# power_connector.net
KiCad netlist of a schematic drawn in Altium Designer
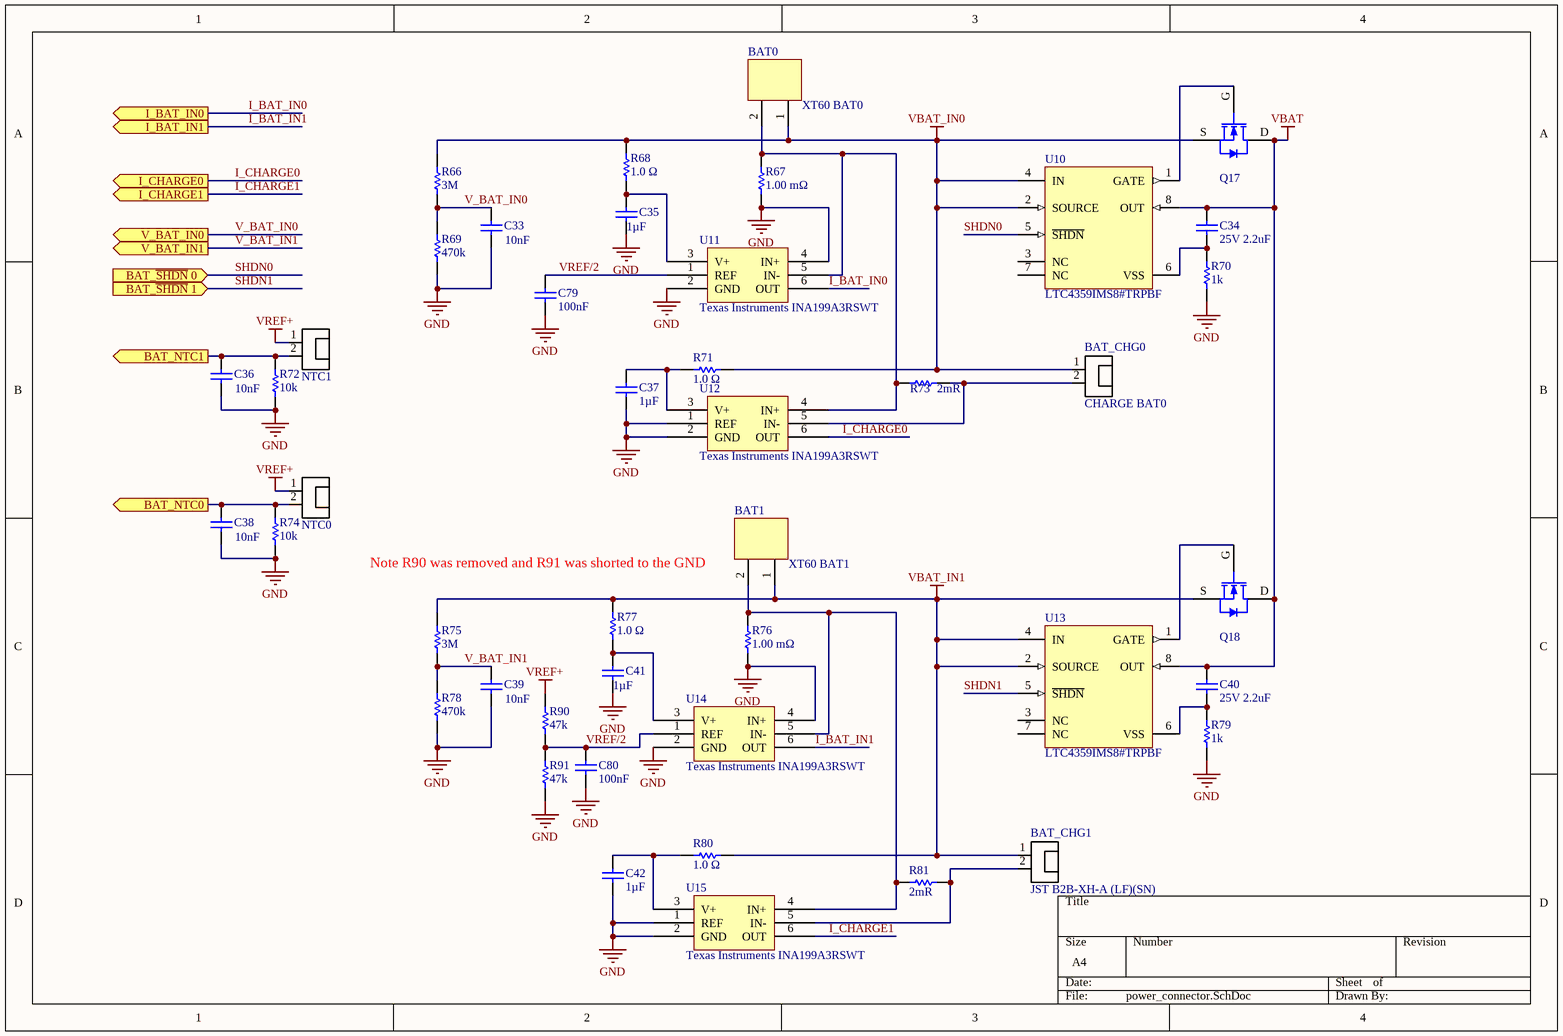
[diagram p0: power_connector.SchDoc]

(export (version "E")
  (design (tool "Eeschema 10.0.6"))
  (components
    (comp (ref "BAT0")
      (value "XT60 BAT0")
      (footprint "PCB-8tmbcd94dx0l5ponnqur-1")
      (description "XT60 Connector Male")
      (libsource (lib "CommunityVault") (part "CMP-d8151592827e07d2-9"))
    )
    (comp (ref "BAT1")
      (value "XT60 BAT1")
      (footprint "PCB-8tmbcd94dx0l5ponnqur-1")
      (description "XT60 Connector Male")
      (libsource (lib "CommunityVault") (part "CMP-d8151592827e07d2-9"))
    )
    (comp (ref "BAT_CHG0")
      (value "CHARGE BAT0")
      (footprint "PCB-s8s8ac3ylnu6waak0fxh-1")
      (description "XH Series 2 Position 2.5 mm Pitch Through Hole Top Entry Shrouded Header")
      (fields (field (name "MANUFACTURER PART NUMBER") "B2B-XH-A (LF)(SN)"))
      (libsource (lib "CommunityVault") (part "SYM-a2a66bdac84f7d61-1"))
    )
    (comp (ref "BAT_CHG1")
      (value "JST B2B-XH-A (LF)(SN)")
      (footprint "PCB-s8s8ac3ylnu6waak0fxh-1")
      (description "XH Series 2 Position 2.5 mm Pitch Through Hole Top Entry Shrouded Header")
      (fields (field (name "MANUFACTURER PART NUMBER") "B2B-XH-A (LF)(SN)"))
      (libsource (lib "CommunityVault") (part "SYM-a2a66bdac84f7d61-1"))
    )
    (comp (ref "C33")
      (value "10nF")
      (footprint "RESC1005X40X25LL05T05")
      (description "0.01uF Capacitor")
      (fields (field (name "MANUFACTURER PART NUMBER") "04025C103KAT2A"))
      (libsource (lib "CommunityVault") (part "CMP-16527022-3"))
    )
    (comp (ref "C34")
      (value "25V 2.2uF")
      (footprint "C0805")
      (description "0805 2.2 uF 25 V ±10 % Tolerance X7R SMT Multilayer Ceramic Capacitor")
      (fields (field (name "MANUFACTURER PART NUMBER") "CC0805KKX7R8BB225"))
      (libsource (lib "CommunityVault") (part "CAP-NP-2"))
    )
    (comp (ref "C35")
      (value "1µF")
      (footprint "CAPC1608X90X35LL15T15")
      (description "0603 1 uF 16 V ±10 % Tolerance X5R SMT Multilayer Ceramic Capacitor")
      (libsource (lib "CommunityVault") (part "CAP-NP-2"))
    )
    (comp (ref "C36")
      (value "10nF")
      (footprint "RESC1005X40X25LL05T05")
      (description "0.01uF Capacitor")
      (fields (field (name "MANUFACTURER PART NUMBER") "04025C103KAT2A"))
      (libsource (lib "CommunityVault") (part "CMP-16527022-3"))
    )
    (comp (ref "C37")
      (value "1µF")
      (footprint "CAPC1608X90X35LL15T15")
      (description "0603 1 uF 16 V ±10 % Tolerance X5R SMT Multilayer Ceramic Capacitor")
      (libsource (lib "CommunityVault") (part "CAP-NP-2"))
    )
    (comp (ref "C38")
      (value "10nF")
      (footprint "RESC1005X40X25LL05T05")
      (description "0.01uF Capacitor")
      (fields (field (name "MANUFACTURER PART NUMBER") "04025C103KAT2A"))
      (libsource (lib "CommunityVault") (part "CMP-16527022-3"))
    )
    (comp (ref "C39")
      (value "10nF")
      (footprint "RESC1005X40X25LL05T05")
      (description "0.01uF Capacitor")
      (fields (field (name "MANUFACTURER PART NUMBER") "04025C103KAT2A"))
      (libsource (lib "CommunityVault") (part "CMP-16527022-3"))
    )
    (comp (ref "C40")
      (value "25V 2.2uF")
      (footprint "C0805")
      (description "0805 2.2 uF 25 V ±10 % Tolerance X7R SMT Multilayer Ceramic Capacitor")
      (fields (field (name "MANUFACTURER PART NUMBER") "CC0805KKX7R8BB225"))
      (libsource (lib "CommunityVault") (part "CAP-NP-2"))
    )
    (comp (ref "C41")
      (value "1µF")
      (footprint "CAPC1608X90X35LL15T15")
      (description "0603 1 uF 16 V ±10 % Tolerance X5R SMT Multilayer Ceramic Capacitor")
      (libsource (lib "CommunityVault") (part "CAP-NP-2"))
    )
    (comp (ref "C42")
      (value "1µF")
      (footprint "CAPC1608X90X35LL15T15")
      (description "0603 1 uF 16 V ±10 % Tolerance X5R SMT Multilayer Ceramic Capacitor")
      (libsource (lib "CommunityVault") (part "CAP-NP-2"))
    )
    (comp (ref "C79")
      (value "100nF")
      (footprint "CAPC1005X56X25NL10T15")
      (description "Ceramic capacitor SMD-0402 100nF /16V X7R# K +-10%, Samsung, RoHS")
      (libsource (lib "CommunityVault") (part "SYM-7bbdb0ed648ba47a-1"))
    )
    (comp (ref "C80")
      (value "100nF")
      (footprint "CAPC1005X56X25NL10T15")
      (description "Ceramic capacitor SMD-0402 100nF /16V X7R# K +-10%, Samsung, RoHS")
      (libsource (lib "CommunityVault") (part "SYM-7bbdb0ed648ba47a-1"))
    )
    (comp (ref "NTC0")
      (value "JST B2B-XH-A (LF)(SN)")
      (footprint "PCB-s8s8ac3ylnu6waak0fxh-1")
      (description "XH Series 2 Position 2.5 mm Pitch Through Hole Top Entry Shrouded Header")
      (fields (field (name "MANUFACTURER PART NUMBER") "B2B-XH-A (LF)(SN)"))
      (libsource (lib "CommunityVault") (part "SYM-a2a66bdac84f7d61-1"))
    )
    (comp (ref "NTC1")
      (value "JST B2B-XH-A (LF)(SN)")
      (footprint "PCB-s8s8ac3ylnu6waak0fxh-1")
      (description "XH Series 2 Position 2.5 mm Pitch Through Hole Top Entry Shrouded Header")
      (fields (field (name "MANUFACTURER PART NUMBER") "B2B-XH-A (LF)(SN)"))
      (libsource (lib "CommunityVault") (part "SYM-a2a66bdac84f7d61-1"))
    )
    (comp (ref "Q17")
      (value "SYM-77c1bbb3bdeca806-1")
      (footprint "PCB-0cgmvcmmtwpbvwdhxnni-1")
      (description "Trans MOSFET N-CH 60V 42.8A 8-Pin PowerPAK SO-DC EP T/R")
      (fields (field (name "MANUFACTURER PART NUMBER") "SIDR626DP-T1-GE3"))
      (libsource (lib "CommunityVault") (part "SYM-77c1bbb3bdeca806-1"))
    )
    (comp (ref "Q18")
      (value "SYM-77c1bbb3bdeca806-1")
      (footprint "PCB-0cgmvcmmtwpbvwdhxnni-1")
      (description "Trans MOSFET N-CH 60V 42.8A 8-Pin PowerPAK SO-DC EP T/R")
      (fields (field (name "MANUFACTURER PART NUMBER") "SIDR626DP-T1-GE3"))
      (libsource (lib "CommunityVault") (part "SYM-77c1bbb3bdeca806-1"))
    )
    (comp (ref "R66")
      (value "3M")
      (footprint "RESC1608X55X30LL15T15")
      (description "Thick Film Resistors - SMD 0603 3Mohms 5% Tol")
      (fields (field (name "MANUFACTURER PART NUMBER") "ERJ-3GEYJ305V"))
      (libsource (lib "CommunityVault") (part "CMP-3654610-2"))
    )
    (comp (ref "R67")
      (value "1.00 mΩ")
      (footprint "PCB-wws5gc0zzodyoofoa1sn-1")
      (description "Res Thick Film 2512 0.001 Ohm 1% 3W ±50ppm/C Pad SMD Automotive T/R")
      (fields (field (name "MANUFACTURER PART NUMBER") "CRE2512-FZ-R001E-3"))
      (libsource (lib "CommunityVault") (part "CMP-5c9b974035f1835c-1"))
    )
    (comp (ref "R68")
      (value "1.0 Ω")
      (footprint "RESC1609X50X30LL10T20")
      (description "RES SMD 1 OHM 5% 1/10W 0603")
      (fields (field (name "MANUFACTURER PART NUMBER") "CRCW06031R00JNEA"))
      (libsource (lib "CommunityVault") (part "CMP-1856057-2"))
    )
    (comp (ref "R69")
      (value "470k")
      (footprint "RESC1609X55X30LL10T20")
      (description "Res Thick Film 0603 1M Ohm 1% 0.33W(1/3W) ±100ppm/°C Pad SMD Automotive T/R")
      (fields (field (name "MANUFACTURER PART NUMBER") "CRCW06031M00FKEAHP"))
      (libsource (lib "CommunityVault") (part "CMP-d1221a8dcd300ee5-2"))
    )
    (comp (ref "R70")
      (value "1k")
      (footprint "RESC1608X55X30NL15T15")
      (description "Res Thick Film 0603 1K Ohm 5% 1/10W ±100ppm/°C Molded SMD SMD Paper T/R")
      (libsource (lib "CommunityVault") (part "CMP-68a0a2e72c4eb767-21"))
    )
    (comp (ref "R71")
      (value "1.0 Ω")
      (footprint "RESC1609X50X30LL10T20")
      (description "RES SMD 1 OHM 5% 1/10W 0603")
      (fields (field (name "MANUFACTURER PART NUMBER") "CRCW06031R00JNEA"))
      (libsource (lib "CommunityVault") (part "CMP-1856057-2"))
    )
    (comp (ref "R72")
      (value "10k")
      (footprint "RESC1608X55X30NL15T15")
      (description "Res Thin Film 0603 10K Ohm 1% 1/16W ±50ppm/°C Molded SMD SMD Paper T/R")
      (libsource (lib "CommunityVault") (part "RES-2"))
    )
    (comp (ref "R73")
      (value "2mR")
      (footprint "RESC3216X89X51ML25T25")
      (description "Res Metal Strip 1206 0.02 Ohm 1% 0.25W(1/4W) ±75ppm/C Molded SMD Automotive Embossed Plastic T/R")
      (fields (field (name "MANUFACTURER PART NUMBER") "WSL1206R0200FEA"))
      (libsource (lib "CommunityVault") (part "CMP-1863047-2"))
    )
    (comp (ref "R74")
      (value "10k")
      (footprint "RESC1608X55X30NL15T15")
      (description "Res Thin Film 0603 10K Ohm 1% 1/16W ±50ppm/°C Molded SMD SMD Paper T/R")
      (libsource (lib "CommunityVault") (part "RES-2"))
    )
    (comp (ref "R75")
      (value "3M")
      (footprint "RESC1608X55X30LL15T15")
      (description "Thick Film Resistors - SMD 0603 3Mohms 5% Tol")
      (fields (field (name "MANUFACTURER PART NUMBER") "ERJ-3GEYJ305V"))
      (libsource (lib "CommunityVault") (part "CMP-3654610-2"))
    )
    (comp (ref "R76")
      (value "1.00 mΩ")
      (footprint "PCB-wws5gc0zzodyoofoa1sn-1")
      (description "Res Thick Film 2512 0.001 Ohm 1% 3W ±50ppm/C Pad SMD Automotive T/R")
      (fields (field (name "MANUFACTURER PART NUMBER") "CRE2512-FZ-R001E-3"))
      (libsource (lib "CommunityVault") (part "CMP-5c9b974035f1835c-1"))
    )
    (comp (ref "R77")
      (value "1.0 Ω")
      (footprint "RESC1609X50X30LL10T20")
      (description "RES SMD 1 OHM 5% 1/10W 0603")
      (fields (field (name "MANUFACTURER PART NUMBER") "CRCW06031R00JNEA"))
      (libsource (lib "CommunityVault") (part "CMP-1856057-2"))
    )
    (comp (ref "R78")
      (value "470k")
      (footprint "RESC1609X55X30LL10T20")
      (description "Res Thick Film 0603 1M Ohm 1% 0.33W(1/3W) ±100ppm/°C Pad SMD Automotive T/R")
      (fields (field (name "MANUFACTURER PART NUMBER") "CRCW06031M00FKEAHP"))
      (libsource (lib "CommunityVault") (part "CMP-d1221a8dcd300ee5-2"))
    )
    (comp (ref "R79")
      (value "1k")
      (footprint "RESC1608X55X30NL15T15")
      (description "Res Thick Film 0603 1K Ohm 5% 1/10W ±100ppm/°C Molded SMD SMD Paper T/R")
      (libsource (lib "CommunityVault") (part "CMP-68a0a2e72c4eb767-21"))
    )
    (comp (ref "R80")
      (value "1.0 Ω")
      (footprint "RESC1609X50X30LL10T20")
      (description "RES SMD 1 OHM 5% 1/10W 0603")
      (fields (field (name "MANUFACTURER PART NUMBER") "CRCW06031R00JNEA"))
      (libsource (lib "CommunityVault") (part "CMP-1856057-2"))
    )
    (comp (ref "R81")
      (value "2mR")
      (footprint "RESC3216X89X51ML25T25")
      (description "Res Metal Strip 1206 0.02 Ohm 1% 0.25W(1/4W) ±75ppm/C Molded SMD Automotive Embossed Plastic T/R")
      (fields (field (name "MANUFACTURER PART NUMBER") "WSL1206R0200FEA"))
      (libsource (lib "CommunityVault") (part "CMP-1863047-2"))
    )
    (comp (ref "R90")
      (value "47k")
      (footprint "RESC1005X40X25LL05T10")
      (description "Thick Film Resistors - SMD 1/8watt 47Kohms 1% 100ppm High Power")
      (fields (field (name "MANUFACTURER PART NUMBER") "CRCW040247K0FKEDHP"))
      (libsource (lib "CommunityVault") (part "CMP-1859043-2"))
    )
    (comp (ref "R91")
      (value "47k")
      (footprint "RESC1005X40X25LL05T10")
      (description "Thick Film Resistors - SMD 1/8watt 47Kohms 1% 100ppm High Power")
      (fields (field (name "MANUFACTURER PART NUMBER") "CRCW040247K0FKEDHP"))
      (libsource (lib "CommunityVault") (part "CMP-1859043-2"))
    )
    (comp (ref "U10")
      (value "LTC4359IMS8#TRPBF")
      (footprint "LT-MS8-8_L")
      (libsource (lib "CommunityVault") (part "LT-LTC4359-MS8-8"))
    )
    (comp (ref "U11")
      (value "Texas Instruments INA199A3RSWT")
      (footprint "PCB-dzg43p1s5wcf61j10amz-1")
      (libsource (lib "CommunityVault") (part "SYM-0f05c77d0cddd0c2-7"))
    )
    (comp (ref "U12")
      (value "Texas Instruments INA199A3RSWT")
      (footprint "PCB-dzg43p1s5wcf61j10amz-1")
      (libsource (lib "CommunityVault") (part "SYM-0f05c77d0cddd0c2-7"))
    )
    (comp (ref "U13")
      (value "LTC4359IMS8#TRPBF")
      (footprint "LT-MS8-8_L")
      (libsource (lib "CommunityVault") (part "LT-LTC4359-MS8-8"))
    )
    (comp (ref "U14")
      (value "Texas Instruments INA199A3RSWT")
      (footprint "PCB-dzg43p1s5wcf61j10amz-1")
      (libsource (lib "CommunityVault") (part "SYM-0f05c77d0cddd0c2-7"))
    )
    (comp (ref "U15")
      (value "Texas Instruments INA199A3RSWT")
      (footprint "PCB-dzg43p1s5wcf61j10amz-1")
      (libsource (lib "CommunityVault") (part "SYM-0f05c77d0cddd0c2-7"))
    )
  )
  (nets
    (net (code "1") (name "/BAT_NTC0") (class "Default")
      (node (ref "C38") (pin "2") (pinfunction "2_2") (pintype "passive"))
      (node (ref "NTC0") (pin "2") (pinfunction "2_2") (pintype "passive"))
      (node (ref "R74") (pin "1") (pinfunction "1_1") (pintype "passive"))
    )
    (net (code "2") (name "/BAT_NTC1") (class "Default")
      (node (ref "C36") (pin "2") (pinfunction "2_2") (pintype "passive"))
      (node (ref "NTC1") (pin "2") (pinfunction "2_2") (pintype "passive"))
      (node (ref "R72") (pin "2") (pinfunction "2_2") (pintype "passive"))
    )
    (net (code "3") (name "/I_BAT_IN0") (class "Default")
      (node (ref "U11") (pin "6") (pinfunction "OUT_6") (pintype "passive"))
    )
    (net (code "4") (name "/I_BAT_IN1") (class "Default")
      (node (ref "U14") (pin "6") (pinfunction "OUT_6") (pintype "passive"))
    )
    (net (code "5") (name "/I_CHARGE0") (class "Default")
      (node (ref "U12") (pin "6") (pinfunction "OUT_6") (pintype "passive"))
    )
    (net (code "6") (name "/I_CHARGE1") (class "Default")
      (node (ref "U15") (pin "6") (pinfunction "OUT_6") (pintype "passive"))
    )
    (net (code "7") (name "/SHDN0") (class "Default")
      (node (ref "U10") (pin "5") (pinfunction "~{SHDN}_5") (pintype "input"))
    )
    (net (code "8") (name "/SHDN1") (class "Default")
      (node (ref "U13") (pin "5") (pinfunction "~{SHDN}_5") (pintype "input"))
    )
    (net (code "9") (name "/VREF{slash}2") (class "Default")
      (node (ref "C79") (pin "1") (pinfunction "1_1") (pintype "passive"))
      (node (ref "C80") (pin "1") (pinfunction "1_1") (pintype "passive"))
      (node (ref "R90") (pin "1") (pinfunction "1_1") (pintype "passive"))
      (node (ref "R91") (pin "2") (pinfunction "2_2") (pintype "passive"))
      (node (ref "U11") (pin "1") (pinfunction "REF_1") (pintype "passive"))
      (node (ref "U14") (pin "1") (pinfunction "REF_1") (pintype "passive"))
    )
    (net (code "10") (name "/V_BAT_IN0") (class "Default")
      (node (ref "C33") (pin "2") (pinfunction "2_2") (pintype "passive"))
      (node (ref "R66") (pin "1") (pinfunction "1_1") (pintype "passive"))
      (node (ref "R69") (pin "2") (pinfunction "2_2") (pintype "passive"))
    )
    (net (code "11") (name "/V_BAT_IN1") (class "Default")
      (node (ref "C39") (pin "2") (pinfunction "2_2") (pintype "passive"))
      (node (ref "R75") (pin "1") (pinfunction "1_1") (pintype "passive"))
      (node (ref "R78") (pin "2") (pinfunction "2_2") (pintype "passive"))
    )
    (net (code "12") (name "GND") (class "Default")
      (node (ref "C33") (pin "1") (pinfunction "1_1") (pintype "passive"))
      (node (ref "C35") (pin "2") (pinfunction "2_2") (pintype "passive"))
      (node (ref "C36") (pin "1") (pinfunction "1_1") (pintype "passive"))
      (node (ref "C37") (pin "2") (pinfunction "2_2") (pintype "passive"))
      (node (ref "C38") (pin "1") (pinfunction "1_1") (pintype "passive"))
      (node (ref "C39") (pin "1") (pinfunction "1_1") (pintype "passive"))
      (node (ref "C41") (pin "2") (pinfunction "2_2") (pintype "passive"))
      (node (ref "C42") (pin "2") (pinfunction "2_2") (pintype "passive"))
      (node (ref "C79") (pin "2") (pinfunction "2_2") (pintype "passive"))
      (node (ref "C80") (pin "2") (pinfunction "2_2") (pintype "passive"))
      (node (ref "R67") (pin "1") (pinfunction "1_1") (pintype "passive"))
      (node (ref "R69") (pin "1") (pinfunction "1_1") (pintype "passive"))
      (node (ref "R70") (pin "1") (pinfunction "1_1") (pintype "passive"))
      (node (ref "R72") (pin "1") (pinfunction "1_1") (pintype "passive"))
      (node (ref "R74") (pin "2") (pinfunction "2_2") (pintype "passive"))
      (node (ref "R76") (pin "1") (pinfunction "1_1") (pintype "passive"))
      (node (ref "R78") (pin "1") (pinfunction "1_1") (pintype "passive"))
      (node (ref "R79") (pin "1") (pinfunction "1_1") (pintype "passive"))
      (node (ref "R91") (pin "1") (pinfunction "1_1") (pintype "passive"))
      (node (ref "U11") (pin "2") (pinfunction "GND_2") (pintype "passive"))
      (node (ref "U11") (pin "4") (pinfunction "IN+_4") (pintype "passive"))
      (node (ref "U12") (pin "1") (pinfunction "REF_1") (pintype "passive"))
      (node (ref "U12") (pin "2") (pinfunction "GND_2") (pintype "passive"))
      (node (ref "U14") (pin "2") (pinfunction "GND_2") (pintype "passive"))
      (node (ref "U14") (pin "4") (pinfunction "IN+_4") (pintype "passive"))
      (node (ref "U15") (pin "1") (pinfunction "REF_1") (pintype "passive"))
      (node (ref "U15") (pin "2") (pinfunction "GND_2") (pintype "passive"))
    )
    (net (code "13") (name "Net-(U10-GATE)") (class "Default")
      (node (ref "Q17") (pin "G") (pinfunction "G_G") (pintype "passive"))
      (node (ref "U10") (pin "1") (pinfunction "GATE_1") (pintype "output"))
    )
    (net (code "14") (name "Net-(U10-VSS)") (class "Default")
      (node (ref "C34") (pin "2") (pinfunction "2_2") (pintype "passive"))
      (node (ref "R70") (pin "2") (pinfunction "2_2") (pintype "passive"))
      (node (ref "U10") (pin "6") (pinfunction "VSS_6") (pintype "power_in"))
    )
    (net (code "15") (name "Net-(U11-IN-)") (class "Default")
      (node (ref "BAT0") (pin "2") (pinfunction "2_2") (pintype "passive"))
      (node (ref "R67") (pin "2") (pinfunction "2_2") (pintype "passive"))
      (node (ref "R73") (pin "2") (pinfunction "2_2") (pintype "passive"))
      (node (ref "U11") (pin "5") (pinfunction "IN-_5") (pintype "passive"))
      (node (ref "U12") (pin "4") (pinfunction "IN+_4") (pintype "passive"))
    )
    (net (code "16") (name "Net-(U11-V+)") (class "Default")
      (node (ref "C35") (pin "1") (pinfunction "1_1") (pintype "passive"))
      (node (ref "R68") (pin "1") (pinfunction "1_1") (pintype "passive"))
      (node (ref "U11") (pin "3") (pinfunction "V+_3") (pintype "passive"))
    )
    (net (code "17") (name "Net-(U12-IN-)") (class "Default")
      (node (ref "BAT_CHG0") (pin "2") (pinfunction "2_2") (pintype "passive"))
      (node (ref "R73") (pin "1") (pinfunction "1_1") (pintype "passive"))
      (node (ref "U12") (pin "5") (pinfunction "IN-_5") (pintype "passive"))
    )
    (net (code "18") (name "Net-(U12-V+)") (class "Default")
      (node (ref "C37") (pin "1") (pinfunction "1_1") (pintype "passive"))
      (node (ref "R71") (pin "1") (pinfunction "1_1") (pintype "passive"))
      (node (ref "U12") (pin "3") (pinfunction "V+_3") (pintype "passive"))
    )
    (net (code "19") (name "Net-(U13-GATE)") (class "Default")
      (node (ref "Q18") (pin "G") (pinfunction "G_G") (pintype "passive"))
      (node (ref "U13") (pin "1") (pinfunction "GATE_1") (pintype "output"))
    )
    (net (code "20") (name "Net-(U13-VSS)") (class "Default")
      (node (ref "C40") (pin "2") (pinfunction "2_2") (pintype "passive"))
      (node (ref "R79") (pin "2") (pinfunction "2_2") (pintype "passive"))
      (node (ref "U13") (pin "6") (pinfunction "VSS_6") (pintype "power_in"))
    )
    (net (code "21") (name "Net-(U14-IN-)") (class "Default")
      (node (ref "BAT1") (pin "2") (pinfunction "2_2") (pintype "passive"))
      (node (ref "R76") (pin "2") (pinfunction "2_2") (pintype "passive"))
      (node (ref "R81") (pin "1") (pinfunction "1_1") (pintype "passive"))
      (node (ref "U14") (pin "5") (pinfunction "IN-_5") (pintype "passive"))
      (node (ref "U15") (pin "4") (pinfunction "IN+_4") (pintype "passive"))
    )
    (net (code "22") (name "Net-(U14-V+)") (class "Default")
      (node (ref "C41") (pin "1") (pinfunction "1_1") (pintype "passive"))
      (node (ref "R77") (pin "1") (pinfunction "1_1") (pintype "passive"))
      (node (ref "U14") (pin "3") (pinfunction "V+_3") (pintype "passive"))
    )
    (net (code "23") (name "Net-(U15-IN-)") (class "Default")
      (node (ref "BAT_CHG1") (pin "2") (pinfunction "2_2") (pintype "passive"))
      (node (ref "R81") (pin "2") (pinfunction "2_2") (pintype "passive"))
      (node (ref "U15") (pin "5") (pinfunction "IN-_5") (pintype "passive"))
    )
    (net (code "24") (name "Net-(U15-V+)") (class "Default")
      (node (ref "C42") (pin "1") (pinfunction "1_1") (pintype "passive"))
      (node (ref "R80") (pin "1") (pinfunction "1_1") (pintype "passive"))
      (node (ref "U15") (pin "3") (pinfunction "V+_3") (pintype "passive"))
    )
    (net (code "25") (name "VBAT") (class "Default")
      (node (ref "C34") (pin "1") (pinfunction "1_1") (pintype "passive"))
      (node (ref "C40") (pin "1") (pinfunction "1_1") (pintype "passive"))
      (node (ref "Q17") (pin "D") (pinfunction "D_D") (pintype "passive"))
      (node (ref "Q18") (pin "D") (pinfunction "D_D") (pintype "passive"))
      (node (ref "U10") (pin "8") (pinfunction "OUT_8") (pintype "input"))
      (node (ref "U13") (pin "8") (pinfunction "OUT_8") (pintype "input"))
    )
    (net (code "26") (name "VBAT_IN0") (class "Default")
      (node (ref "BAT0") (pin "1") (pinfunction "1_1") (pintype "passive"))
      (node (ref "BAT_CHG0") (pin "1") (pinfunction "1_1") (pintype "passive"))
      (node (ref "Q17") (pin "S") (pinfunction "S_S") (pintype "passive"))
      (node (ref "R66") (pin "2") (pinfunction "2_2") (pintype "passive"))
      (node (ref "R68") (pin "2") (pinfunction "2_2") (pintype "passive"))
      (node (ref "R71") (pin "2") (pinfunction "2_2") (pintype "passive"))
      (node (ref "U10") (pin "2") (pinfunction "SOURCE_2") (pintype "input"))
      (node (ref "U10") (pin "4") (pinfunction "IN_4") (pintype "power_in"))
    )
    (net (code "27") (name "VBAT_IN1") (class "Default")
      (node (ref "BAT1") (pin "1") (pinfunction "1_1") (pintype "passive"))
      (node (ref "BAT_CHG1") (pin "1") (pinfunction "1_1") (pintype "passive"))
      (node (ref "Q18") (pin "S") (pinfunction "S_S") (pintype "passive"))
      (node (ref "R75") (pin "2") (pinfunction "2_2") (pintype "passive"))
      (node (ref "R77") (pin "2") (pinfunction "2_2") (pintype "passive"))
      (node (ref "R80") (pin "2") (pinfunction "2_2") (pintype "passive"))
      (node (ref "U13") (pin "2") (pinfunction "SOURCE_2") (pintype "input"))
      (node (ref "U13") (pin "4") (pinfunction "IN_4") (pintype "power_in"))
    )
    (net (code "28") (name "VREF+") (class "Default")
      (node (ref "NTC0") (pin "1") (pinfunction "1_1") (pintype "passive"))
      (node (ref "NTC1") (pin "1") (pinfunction "1_1") (pintype "passive"))
      (node (ref "R90") (pin "2") (pinfunction "2_2") (pintype "passive"))
    )
    (net (code "29") (name "unconnected-(U10-NC-Pad3)") (class "Default")
      (node (ref "U10") (pin "3") (pinfunction "NC_3") (pintype "passive"))
    )
    (net (code "30") (name "unconnected-(U10-NC-Pad7)") (class "Default")
      (node (ref "U10") (pin "7") (pinfunction "NC_7") (pintype "passive"))
    )
    (net (code "31") (name "unconnected-(U13-NC-Pad3)") (class "Default")
      (node (ref "U13") (pin "3") (pinfunction "NC_3") (pintype "passive"))
    )
    (net (code "32") (name "unconnected-(U13-NC-Pad7)") (class "Default")
      (node (ref "U13") (pin "7") (pinfunction "NC_7") (pintype "passive"))
    )
  )
)
